# TEMT6000.net
KiCad netlist of a schematic drawn in EAGLE
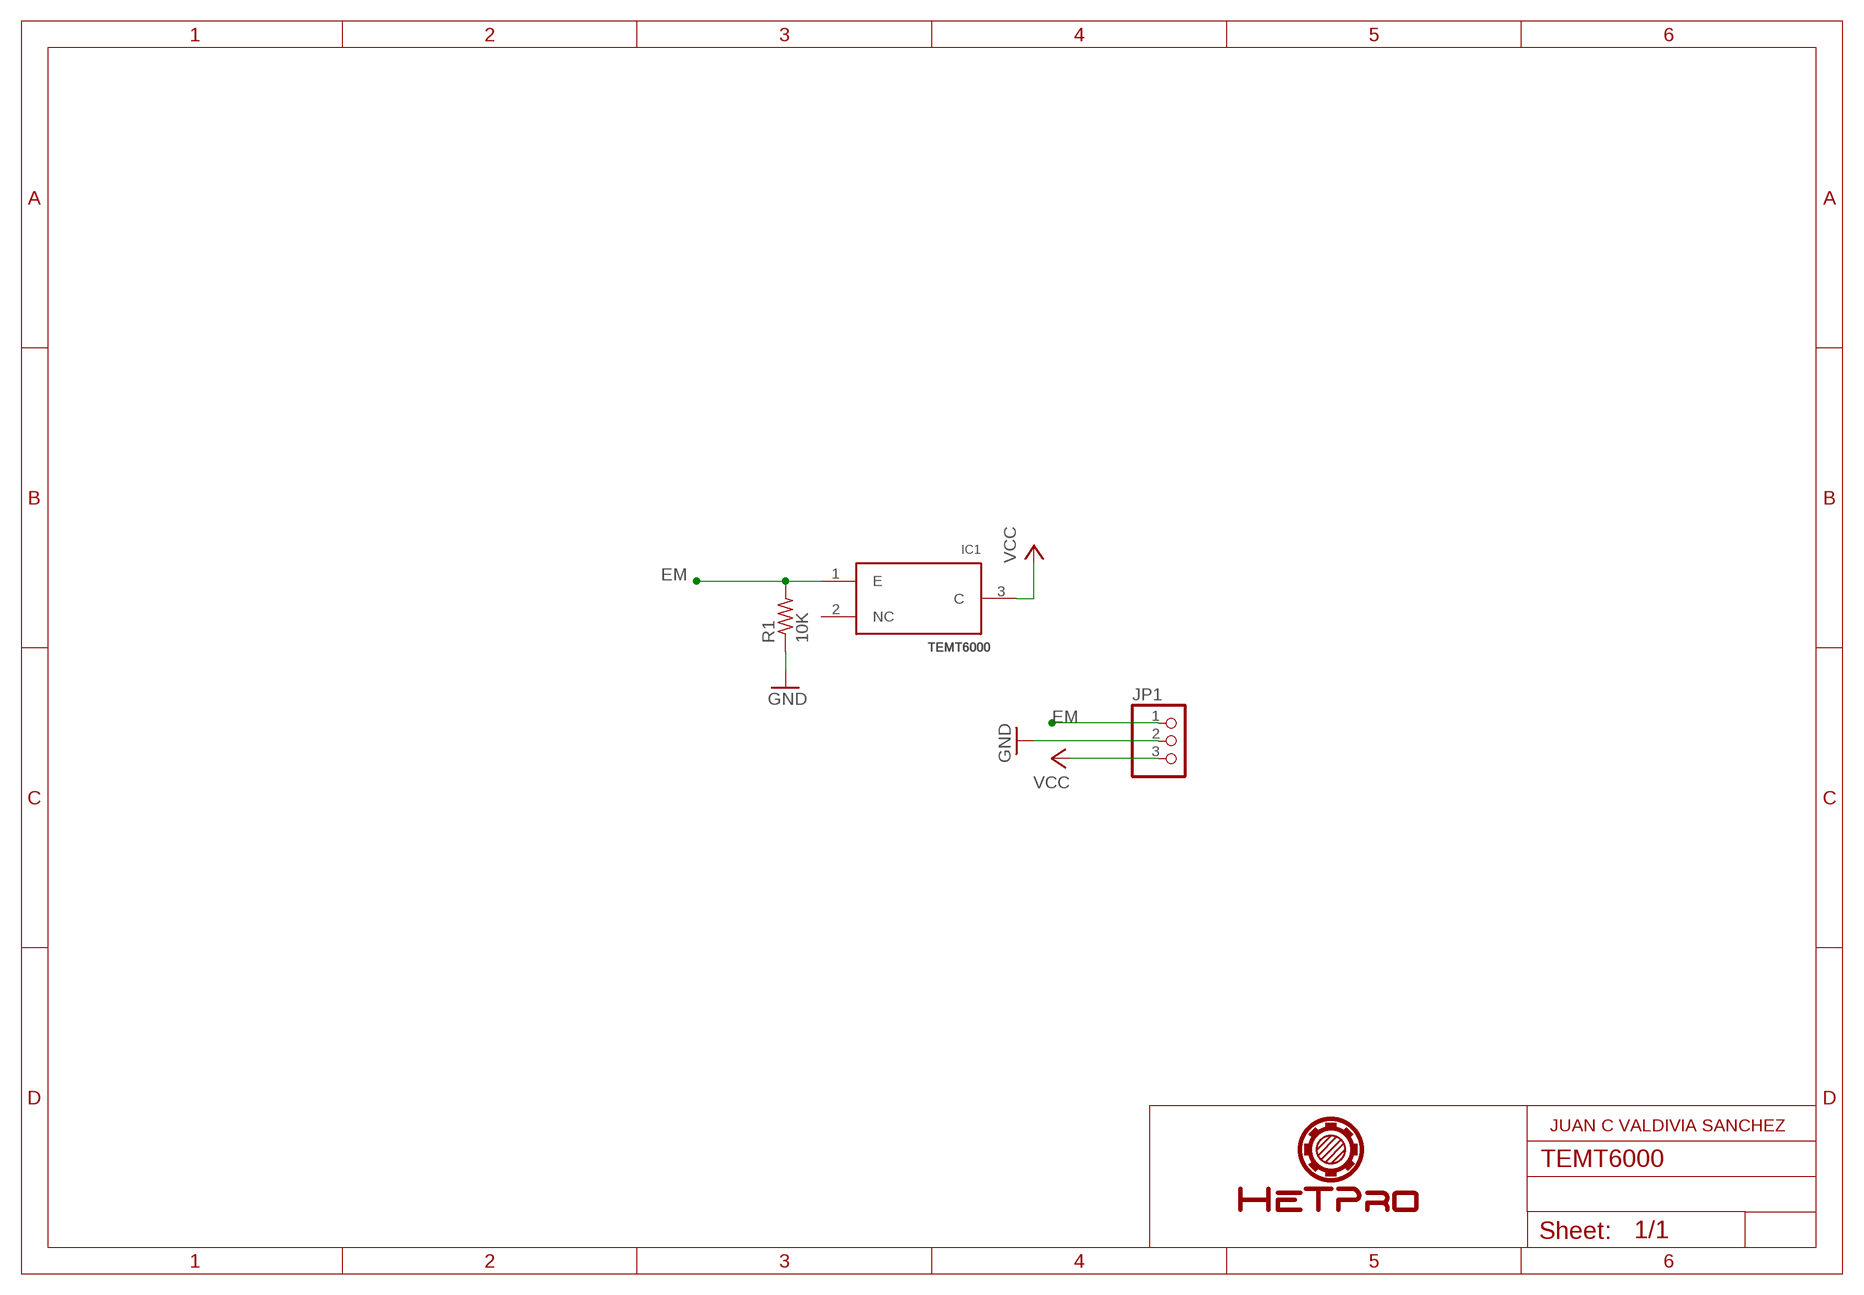
[diagram p0: schematic, sheet 1]

(export (version "E")
  (design (tool "Eeschema 10.0.6"))
  (components
    (comp (ref "IC1")
      (value "TEMT6000")
      (footprint "eagle-import:TEMT6000")
      (libsource (lib "eagle-import") (part "TEMT6000"))
    )
    (comp (ref "JP1")
      (value "PINHD-1X3")
      (footprint "eagle-import:1X03")
      (libsource (lib "eagle-import") (part "PINHD-1X3"))
    )
    (comp (ref "R1")
      (value "10K")
      (footprint "eagle-import:R0603")
      (libsource (lib "eagle-import") (part "R-US_R0603"))
    )
  )
  (nets
    (net (code "1") (name "/EM") (class "Default")
      (node (ref "IC1") (pin "1") (pinfunction "E_1") (pintype "bidirectional"))
      (node (ref "JP1") (pin "1") (pinfunction "1_1") (pintype "passive"))
      (node (ref "R1") (pin "2") (pinfunction "2_2") (pintype "passive"))
    )
    (net (code "2") (name "GND") (class "Default")
      (node (ref "JP1") (pin "2") (pinfunction "2_2") (pintype "passive"))
      (node (ref "R1") (pin "1") (pinfunction "1_1") (pintype "passive"))
    )
    (net (code "3") (name "VCC") (class "Default")
      (node (ref "IC1") (pin "3") (pinfunction "C_3") (pintype "bidirectional"))
      (node (ref "JP1") (pin "3") (pinfunction "3_3") (pintype "passive"))
    )
    (net (code "4") (name "unconnected-(IC1-NC-Pad2)") (class "Default")
      (node (ref "IC1") (pin "2") (pinfunction "NC_2") (pintype "bidirectional"))
    )
  )
)
